# ConvertionBoard.net
KiCad netlist of a schematic drawn in Altium Designer
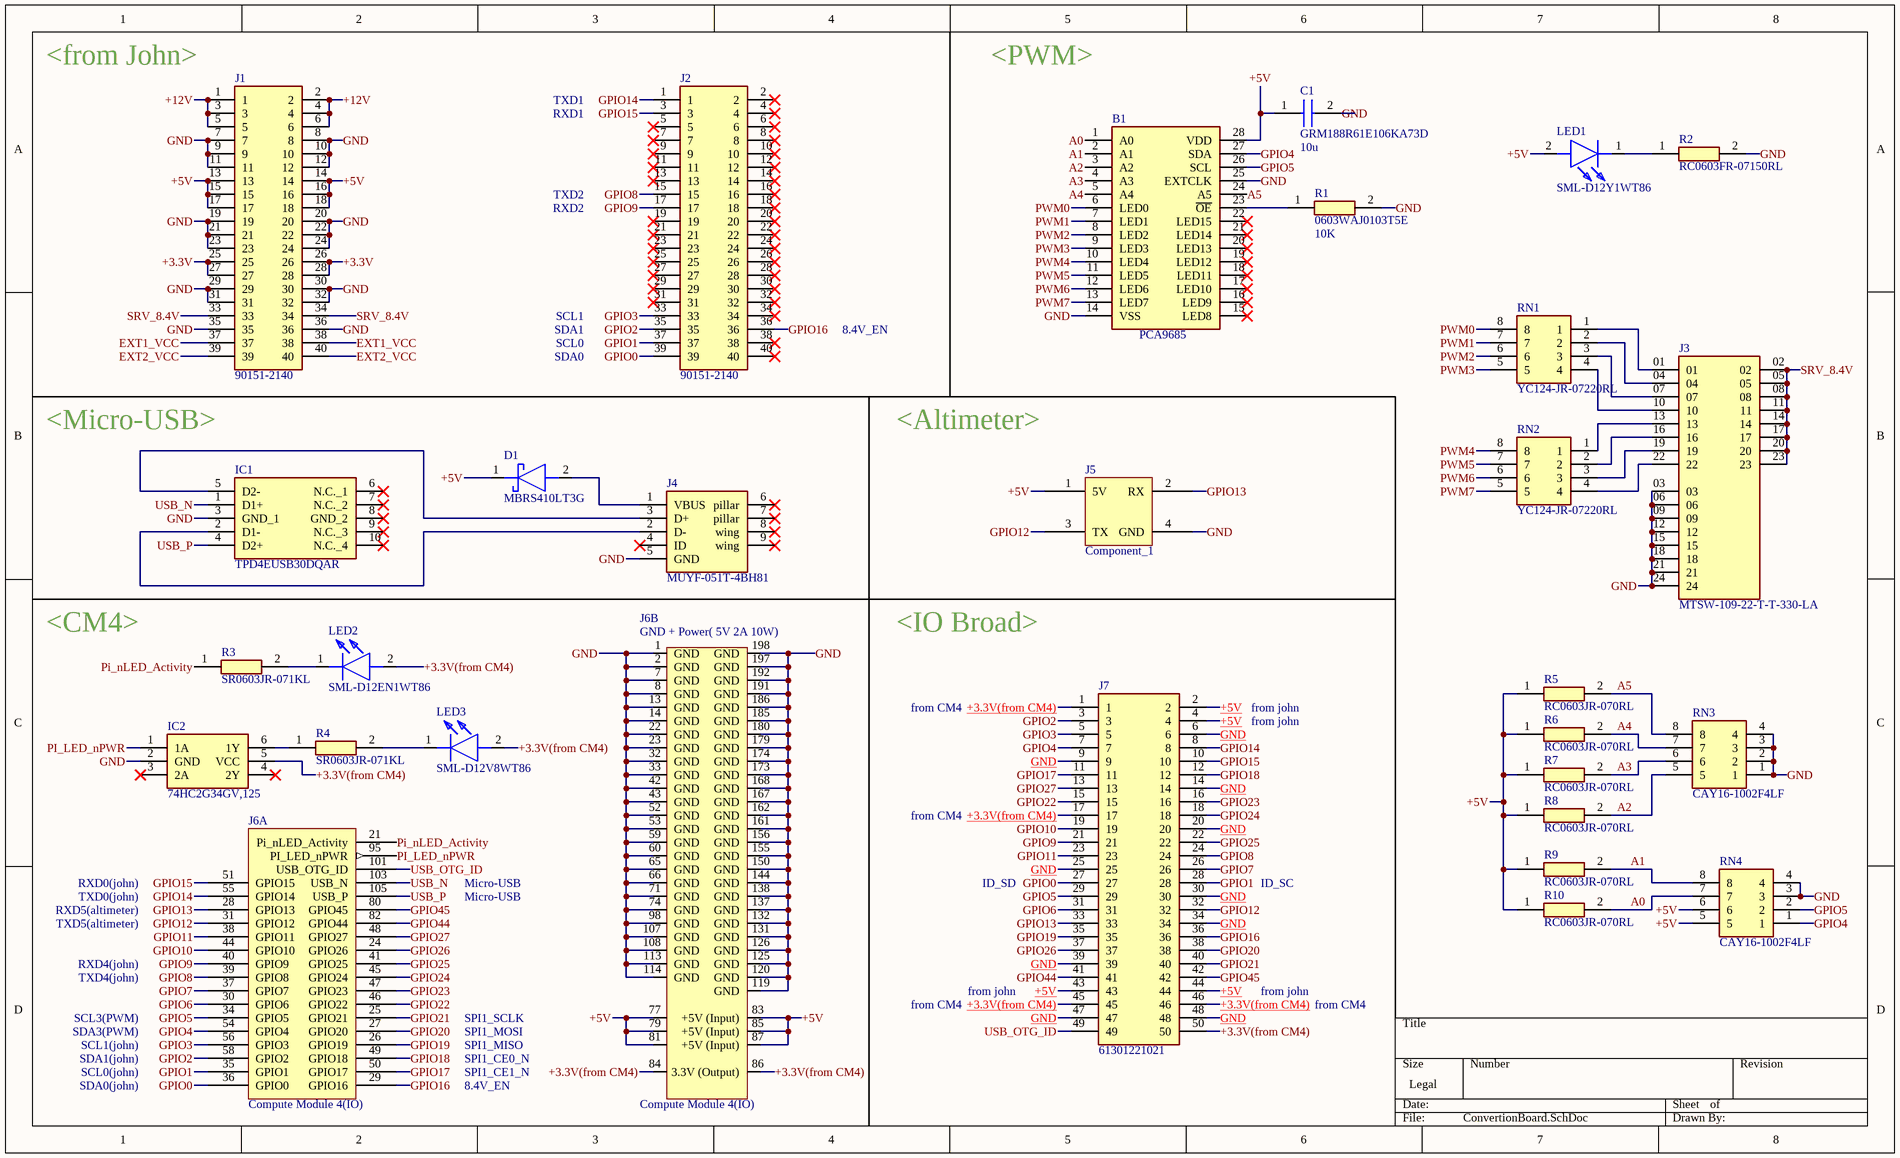
[diagram p0: ConvertionBoard.SchDoc]

(export (version "E")
  (design (tool "Eeschema 10.0.6"))
  (components
    (comp (ref "B1")
      (value "PCA9685")
      (footprint "PCA9685")
      (description "PCA9685PW/Q900,118")
      (fields (field (name "MOUSER PART NUMBER") "771-PCA9685PWQ900118"))
      (libsource (lib "ConvertionBoard") (part "PCA9685"))
    )
    (comp (ref "C1")
      (value "GRM188R61E106KA73D")
      (footprint "ConvertionBoard:GRM18x")
      (description "10% 10uF Capacitor")
      (fields (field (name "MOUSER PART NUMBER") "81-GRM188R61E106KA3D") (field (name "ALTIUM_VALUE") "10u"))
      (libsource (lib "ConvertionBoard") (part "GRM188R61E106KA73D"))
    )
    (comp (ref "D1")
      (value "MBRS410LT3G")
      (footprint "ConvertionBoard:DIOM8059X261N")
      (description "Schottky Diode")
      (fields (field (name "MOUSER PART NUMBER") "863-MBRS410LT3G"))
      (libsource (lib "ConvertionBoard") (part "MBRS410LT3G"))
    )
    (comp (ref "IC1")
      (value "TPD4EUSB30DQAR")
      (footprint "ConvertionBoard:DQA(R-PUSON-N10)")
      (description "Integrated Circuit")
      (fields (field (name "MOUSER PART NUMBER") "595-TPD4EUSB30DQAR"))
      (libsource (lib "ConvertionBoard") (part "TPD4EUSB30DQAR"))
    )
    (comp (ref "IC2")
      (value "74HC2G34GV,125")
      (footprint "ConvertionBoard:SOT95P275X110-6N")
      (description "Integrated Circuit")
      (fields (field (name "MOUSER PART NUMBER") "771-HC2G34GV125"))
      (libsource (lib "ConvertionBoard") (part "74HC2G34GV,125"))
    )
    (comp (ref "J1")
      (value "90151-2140")
      (footprint "RHDR40W70P254_2X20_5065X498X870P")
      (description "Headers")
      (fields (field (name "MOUSER PART NUMBER") "538-90151-2140"))
      (libsource (lib "ConvertionBoard") (part "90151-2140"))
    )
    (comp (ref "J2")
      (value "90151-2140")
      (footprint "RHDR40W70P254_2X20_5065X498X870P")
      (description "Headers")
      (fields (field (name "MOUSER PART NUMBER") "538-90151-2140"))
      (libsource (lib "ConvertionBoard") (part "90151-2140"))
    )
    (comp (ref "J3")
      (value "MTSW-109-22-T-T-330-LA")
      (footprint "SAMTEC_MTSW-109-22-T-T-330-LA")
      (description "PWM model pin")
      (fields (field (name "MF") "Samtec"))
      (libsource (lib "ConvertionBoard") (part "MTSW-109-22-T-T-330-LA"))
    )
    (comp (ref "J4")
      (value "MUYF-051T-4BH81")
      (footprint "ConvertionBoard:473460001")
      (description "Micro USB")
      (fields
        (field (name "MANUFACTURER_PART_NUMBER") "47346-0001")
        (field (name "MOUSER PART NUMBER") "538-47346-0001")
      )
      (libsource (lib "ConvertionBoard") (part "MUYF-051T-4BH81"))
    )
    (comp (ref "J5")
      (value "Component_1")
      (footprint "Component_1")
      (description "Altimeter pin")
      (libsource (lib "ConvertionBoard") (part "Component_1"))
    )
    (comp (ref "J6")
      (value "Compute Module 4(IO)")
      (footprint "CM4-F40C-100DS-0.4v_1.5mm_0mm")
      (libsource (lib "ConvertionBoard") (part "CM4_ALL"))
    )
    (comp (ref "J7")
      (value "61301221021")
      (footprint "ConvertionBoard:61301221021 - output")
      (description "IO broad pin")
      (fields (field (name "MOUSER PART NUMBER") "710-61301221021"))
      (libsource (lib "ConvertionBoard") (part "61301221021"))
    )
    (comp (ref "LED1")
      (value "SML-D12Y1WT86")
      (footprint "ConvertionBoard:LEDC1608X55N")
      (description "Yellow LED (connect with 150ohm)")
      (fields (field (name "MOUSER PART NUMBER") "755-SML-D12Y1WT86"))
      (libsource (lib "ConvertionBoard") (part "SML-D12Y1WT86"))
    )
    (comp (ref "LED2")
      (value "SML-D12EN1WT86")
      (footprint "ConvertionBoard:LEDC1608X55N")
      (description "Green LED (connect with 1Kohm)")
      (fields
        (field (name "MANUFACTURER_PART_NUMBER") "SMLD12EN1WT86")
        (field (name "MOUSER PART NUMBER") "755-SMLD12EN1WT86")
      )
      (libsource (lib "ConvertionBoard") (part "SML-D12EN1WT86"))
    )
    (comp (ref "LED3")
      (value "SML-D12V8WT86")
      (footprint "ConvertionBoard:LEDC1608X55N")
      (description "Red LED (connect with 1Kohm)")
      (fields (field (name "MOUSER PART NUMBER") "755-SML-D12V8WT86"))
      (libsource (lib "ConvertionBoard") (part "SML-D12V8WT86"))
    )
    (comp (ref "R1")
      (value "0603WAJ0103T5E")
      (footprint "RESC1608X55N_10K")
      (description "5% 10K Resistor")
      (fields (field (name "MOUSER PART NUMBER") "303-0603WAJ0103T5E") (field (name "ALTIUM_VALUE") "10K"))
      (libsource (lib "ConvertionBoard") (part "0603WAJ0103T5E"))
    )
    (comp (ref "R2")
      (value "RC0603FR-07150RL")
      (footprint "ConvertionBoard:RESC1608X55N_150")
      (description "1% 150 Resistor")
      (fields (field (name "MOUSER PART NUMBER") "603-RC0603FR-07150RL"))
      (libsource (lib "ConvertionBoard") (part "RC0603FR-07150RL"))
    )
    (comp (ref "R3")
      (value "SR0603JR-071KL")
      (footprint "ConvertionBoard:RESC1608X55N_0")
      (description "5% 1K Resistor")
      (fields
        (field (name "MANUFACTURER_PART_NUMBER") "RC0603JR-070RL")
        (field (name "MOUSER PART NUMBER") "603-RC0603JR-070RL")
      )
      (libsource (lib "ConvertionBoard") (part "SR0603JR-071KL"))
    )
    (comp (ref "R4")
      (value "SR0603JR-071KL")
      (footprint "ConvertionBoard:RESC1608X55N_0")
      (description "5% 1K Resistor")
      (fields
        (field (name "MANUFACTURER_PART_NUMBER") "RC0603JR-070RL")
        (field (name "MOUSER PART NUMBER") "603-RC0603JR-070RL")
      )
      (libsource (lib "ConvertionBoard") (part "SR0603JR-071KL"))
    )
    (comp (ref "R5")
      (value "RC0603JR-070RL")
      (footprint "ConvertionBoard:RESC1608X55N_0")
      (description "5% 0 Resistor")
      (fields (field (name "MOUSER PART NUMBER") "603-RC0603JR-070RL"))
      (libsource (lib "ConvertionBoard") (part "RC0603JR-070RL"))
    )
    (comp (ref "R6")
      (value "RC0603JR-070RL")
      (footprint "ConvertionBoard:RESC1608X55N_0")
      (description "5% 0 Resistor")
      (fields (field (name "MOUSER PART NUMBER") "603-RC0603JR-070RL"))
      (libsource (lib "ConvertionBoard") (part "RC0603JR-070RL"))
    )
    (comp (ref "R7")
      (value "RC0603JR-070RL")
      (footprint "ConvertionBoard:RESC1608X55N_0")
      (description "5% 0 Resistor")
      (fields (field (name "MOUSER PART NUMBER") "603-RC0603JR-070RL"))
      (libsource (lib "ConvertionBoard") (part "RC0603JR-070RL"))
    )
    (comp (ref "R8")
      (value "RC0603JR-070RL")
      (footprint "ConvertionBoard:RESC1608X55N_0")
      (description "5% 0 Resistor")
      (fields (field (name "MOUSER PART NUMBER") "603-RC0603JR-070RL"))
      (libsource (lib "ConvertionBoard") (part "RC0603JR-070RL"))
    )
    (comp (ref "R9")
      (value "RC0603JR-070RL")
      (footprint "ConvertionBoard:RESC1608X55N_0")
      (description "5% 0 Resistor")
      (fields (field (name "MOUSER PART NUMBER") "603-RC0603JR-070RL"))
      (libsource (lib "ConvertionBoard") (part "RC0603JR-070RL"))
    )
    (comp (ref "R10")
      (value "RC0603JR-070RL")
      (footprint "ConvertionBoard:RESC1608X55N_0")
      (description "5% 0 Resistor")
      (fields (field (name "MOUSER PART NUMBER") "603-RC0603JR-070RL"))
      (libsource (lib "ConvertionBoard") (part "RC0603JR-070RL"))
    )
    (comp (ref "RN1")
      (value "YC124-JR-07220RL")
      (footprint "ConvertionBoard:YC124JR07220RL")
      (description "5％ 220 Resistor Network")
      (libsource (lib "") (part "YC124-JR-07220RL_1"))
    )
    (comp (ref "RN2")
      (value "YC124-JR-07220RL")
      (footprint "ConvertionBoard:YC124JR07220RL")
      (description "5％ 220 Resistor Network")
      (libsource (lib "ConvertionBoard") (part "YC124-JR-07220RL"))
    )
    (comp (ref "RN3")
      (value "CAY16-1002F4LF")
      (footprint "ConvertionBoard:CAY-16-F4")
      (description "1% 10K Resistor Network(lab have)")
      (fields (field (name "MOUSER PART NUMBER") "652-CAY16-1002F4LF"))
      (libsource (lib "ConvertionBoard") (part "CAY16-1002F4LF"))
    )
    (comp (ref "RN4")
      (value "CAY16-1002F4LF")
      (footprint "ConvertionBoard:CAY-16-F4")
      (description "1% 10K Resistor Network(lab have)")
      (fields (field (name "MOUSER PART NUMBER") "652-CAY16-1002F4LF"))
      (libsource (lib "ConvertionBoard") (part "CAY16-1002F4LF"))
    )
  )
  (nets
    (net (code "1") (name "/+3.3V") (class "Default")
      (node (ref "J1") (pin "25") (pinfunction "25_25") (pintype "passive"))
      (node (ref "J1") (pin "26") (pinfunction "26_26") (pintype "passive"))
      (node (ref "J1") (pin "27") (pinfunction "27_27") (pintype "passive"))
      (node (ref "J1") (pin "28") (pinfunction "28_28") (pintype "passive"))
    )
    (net (code "2") (name "/+3.3V(from CM4)") (class "Default")
      (node (ref "IC2") (pin "5") (pinfunction "VCC_5") (pintype "passive"))
      (node (ref "J6") (pin "84") (pinfunction "3.3V_(Output)_84") (pintype "power_in"))
      (node (ref "J6") (pin "86") (pinfunction "3.3V_(Output)_86") (pintype "power_in"))
      (node (ref "J7") (pin "1") (pinfunction "1_1") (pintype "passive"))
      (node (ref "J7") (pin "17") (pinfunction "17_17") (pintype "passive"))
      (node (ref "J7") (pin "45") (pinfunction "45_45") (pintype "passive"))
      (node (ref "J7") (pin "46") (pinfunction "46_46") (pintype "passive"))
      (node (ref "J7") (pin "50") (pinfunction "50_50") (pintype "passive"))
      (node (ref "LED2") (pin "2") (pinfunction "A_2") (pintype "passive"))
      (node (ref "LED3") (pin "2") (pinfunction "A_2") (pintype "passive"))
    )
    (net (code "3") (name "/+5V") (class "Default")
      (node (ref "B1") (pin "28") (pinfunction "VDD_28") (pintype "passive"))
      (node (ref "C1") (pin "1") (pinfunction "1_1") (pintype "passive"))
      (node (ref "D1") (pin "1") (pinfunction "K_1") (pintype "passive"))
      (node (ref "J1") (pin "13") (pinfunction "13_13") (pintype "passive"))
      (node (ref "J1") (pin "14") (pinfunction "14_14") (pintype "passive"))
      (node (ref "J1") (pin "15") (pinfunction "15_15") (pintype "passive"))
      (node (ref "J1") (pin "16") (pinfunction "16_16") (pintype "passive"))
      (node (ref "J1") (pin "17") (pinfunction "17_17") (pintype "passive"))
      (node (ref "J1") (pin "18") (pinfunction "18_18") (pintype "passive"))
      (node (ref "J5") (pin "1") (pinfunction "5V_1") (pintype "passive"))
      (node (ref "J6") (pin "77") (pinfunction "+5V_(Input)_77") (pintype "power_in"))
      (node (ref "J6") (pin "79") (pinfunction "+5V_(Input)_79") (pintype "power_in"))
      (node (ref "J6") (pin "81") (pinfunction "+5V_(Input)_81") (pintype "power_in"))
      (node (ref "J6") (pin "83") (pinfunction "+5V_(Input)_83") (pintype "power_in"))
      (node (ref "J6") (pin "85") (pinfunction "+5V_(Input)_85") (pintype "power_in"))
      (node (ref "J6") (pin "87") (pinfunction "+5V_(Input)_87") (pintype "power_in"))
      (node (ref "J7") (pin "2") (pinfunction "2_2") (pintype "passive"))
      (node (ref "J7") (pin "4") (pinfunction "4_4") (pintype "passive"))
      (node (ref "J7") (pin "43") (pinfunction "43_43") (pintype "passive"))
      (node (ref "J7") (pin "44") (pinfunction "44_44") (pintype "passive"))
      (node (ref "LED1") (pin "2") (pinfunction "A_2") (pintype "passive"))
      (node (ref "R10") (pin "1") (pinfunction "1_1") (pintype "passive"))
      (node (ref "R5") (pin "1") (pinfunction "1_1") (pintype "passive"))
      (node (ref "R6") (pin "1") (pinfunction "1_1") (pintype "passive"))
      (node (ref "R7") (pin "1") (pinfunction "1_1") (pintype "passive"))
      (node (ref "R8") (pin "1") (pinfunction "1_1") (pintype "passive"))
      (node (ref "R9") (pin "1") (pinfunction "1_1") (pintype "passive"))
      (node (ref "RN4") (pin "5") (pinfunction "5_5") (pintype "passive"))
      (node (ref "RN4") (pin "6") (pinfunction "6_6") (pintype "passive"))
    )
    (net (code "4") (name "/+12V") (class "Default")
      (node (ref "J1") (pin "1") (pinfunction "1_1") (pintype "passive"))
      (node (ref "J1") (pin "2") (pinfunction "2_2") (pintype "passive"))
      (node (ref "J1") (pin "3") (pinfunction "3_3") (pintype "passive"))
      (node (ref "J1") (pin "4") (pinfunction "4_4") (pintype "passive"))
      (node (ref "J1") (pin "5") (pinfunction "5_5") (pintype "passive"))
      (node (ref "J1") (pin "6") (pinfunction "6_6") (pintype "passive"))
    )
    (net (code "5") (name "/A0") (class "Default")
      (node (ref "B1") (pin "1") (pinfunction "A0_1") (pintype "passive"))
      (node (ref "R10") (pin "2") (pinfunction "2_2") (pintype "passive"))
      (node (ref "RN4") (pin "7") (pinfunction "7_7") (pintype "passive"))
    )
    (net (code "6") (name "/A1") (class "Default")
      (node (ref "B1") (pin "2") (pinfunction "A1_2") (pintype "passive"))
      (node (ref "R9") (pin "2") (pinfunction "2_2") (pintype "passive"))
      (node (ref "RN4") (pin "8") (pinfunction "8_8") (pintype "passive"))
    )
    (net (code "7") (name "/A2") (class "Default")
      (node (ref "B1") (pin "3") (pinfunction "A2_3") (pintype "passive"))
      (node (ref "R8") (pin "2") (pinfunction "2_2") (pintype "passive"))
      (node (ref "RN3") (pin "5") (pinfunction "5_5") (pintype "passive"))
    )
    (net (code "8") (name "/A3") (class "Default")
      (node (ref "B1") (pin "4") (pinfunction "A3_4") (pintype "passive"))
      (node (ref "R7") (pin "2") (pinfunction "2_2") (pintype "passive"))
      (node (ref "RN3") (pin "6") (pinfunction "6_6") (pintype "passive"))
    )
    (net (code "9") (name "/A4") (class "Default")
      (node (ref "B1") (pin "5") (pinfunction "A4_5") (pintype "passive"))
      (node (ref "R6") (pin "2") (pinfunction "2_2") (pintype "passive"))
      (node (ref "RN3") (pin "7") (pinfunction "7_7") (pintype "passive"))
    )
    (net (code "10") (name "/A5") (class "Default")
      (node (ref "B1") (pin "24") (pinfunction "A5_24") (pintype "passive"))
      (node (ref "R5") (pin "2") (pinfunction "2_2") (pintype "passive"))
      (node (ref "RN3") (pin "8") (pinfunction "8_8") (pintype "passive"))
    )
    (net (code "11") (name "/EXT1_VCC") (class "Default")
      (node (ref "J1") (pin "37") (pinfunction "37_37") (pintype "passive"))
      (node (ref "J1") (pin "38") (pinfunction "38_38") (pintype "passive"))
    )
    (net (code "12") (name "/EXT2_VCC") (class "Default")
      (node (ref "J1") (pin "39") (pinfunction "39_39") (pintype "passive"))
      (node (ref "J1") (pin "40") (pinfunction "40_40") (pintype "passive"))
    )
    (net (code "13") (name "/GND") (class "Default")
      (node (ref "B1") (pin "14") (pinfunction "VSS_14") (pintype "passive"))
      (node (ref "B1") (pin "25") (pinfunction "EXTCLK_25") (pintype "passive"))
      (node (ref "C1") (pin "2") (pinfunction "2_2") (pintype "passive"))
      (node (ref "IC1") (pin "3") (pinfunction "GND_1_3") (pintype "passive"))
      (node (ref "IC2") (pin "2") (pinfunction "GND_2") (pintype "passive"))
      (node (ref "J1") (pin "10") (pinfunction "10_10") (pintype "passive"))
      (node (ref "J1") (pin "11") (pinfunction "11_11") (pintype "passive"))
      (node (ref "J1") (pin "12") (pinfunction "12_12") (pintype "passive"))
      (node (ref "J1") (pin "19") (pinfunction "19_19") (pintype "passive"))
      (node (ref "J1") (pin "20") (pinfunction "20_20") (pintype "passive"))
      (node (ref "J1") (pin "21") (pinfunction "21_21") (pintype "passive"))
      (node (ref "J1") (pin "22") (pinfunction "22_22") (pintype "passive"))
      (node (ref "J1") (pin "23") (pinfunction "23_23") (pintype "passive"))
      (node (ref "J1") (pin "24") (pinfunction "24_24") (pintype "passive"))
      (node (ref "J1") (pin "29") (pinfunction "29_29") (pintype "passive"))
      (node (ref "J1") (pin "30") (pinfunction "30_30") (pintype "passive"))
      (node (ref "J1") (pin "31") (pinfunction "31_31") (pintype "passive"))
      (node (ref "J1") (pin "32") (pinfunction "32_32") (pintype "passive"))
      (node (ref "J1") (pin "35") (pinfunction "35_35") (pintype "passive"))
      (node (ref "J1") (pin "36") (pinfunction "36_36") (pintype "passive"))
      (node (ref "J1") (pin "7") (pinfunction "7_7") (pintype "passive"))
      (node (ref "J1") (pin "8") (pinfunction "8_8") (pintype "passive"))
      (node (ref "J1") (pin "9") (pinfunction "9_9") (pintype "passive"))
      (node (ref "J3") (pin "03") (pinfunction "03_03") (pintype "passive"))
      (node (ref "J3") (pin "06") (pinfunction "06_06") (pintype "passive"))
      (node (ref "J3") (pin "09") (pinfunction "09_09") (pintype "passive"))
      (node (ref "J3") (pin "12") (pinfunction "12_12") (pintype "passive"))
      (node (ref "J3") (pin "15") (pinfunction "15_15") (pintype "passive"))
      (node (ref "J3") (pin "18") (pinfunction "18_18") (pintype "passive"))
      (node (ref "J3") (pin "21") (pinfunction "21_21") (pintype "passive"))
      (node (ref "J3") (pin "24") (pinfunction "24_24") (pintype "passive"))
      (node (ref "J4") (pin "5") (pinfunction "GND_5") (pintype "passive"))
      (node (ref "J5") (pin "4") (pinfunction "GND_4") (pintype "passive"))
      (node (ref "J6") (pin "1") (pinfunction "GND_1") (pintype "power_in"))
      (node (ref "J6") (pin "107") (pinfunction "GND_107") (pintype "power_in"))
      (node (ref "J6") (pin "108") (pinfunction "GND_108") (pintype "power_in"))
      (node (ref "J6") (pin "113") (pinfunction "GND_113") (pintype "power_in"))
      (node (ref "J6") (pin "114") (pinfunction "GND_114") (pintype "power_in"))
      (node (ref "J6") (pin "119") (pinfunction "GND_119") (pintype "power_in"))
      (node (ref "J6") (pin "120") (pinfunction "GND_120") (pintype "power_in"))
      (node (ref "J6") (pin "125") (pinfunction "GND_125") (pintype "power_in"))
      (node (ref "J6") (pin "126") (pinfunction "GND_126") (pintype "power_in"))
      (node (ref "J6") (pin "13") (pinfunction "GND_13") (pintype "power_in"))
      (node (ref "J6") (pin "131") (pinfunction "GND_131") (pintype "power_in"))
      (node (ref "J6") (pin "132") (pinfunction "GND_132") (pintype "power_in"))
      (node (ref "J6") (pin "137") (pinfunction "GND_137") (pintype "power_in"))
      (node (ref "J6") (pin "138") (pinfunction "GND_138") (pintype "power_in"))
      (node (ref "J6") (pin "14") (pinfunction "GND_14") (pintype "power_in"))
      (node (ref "J6") (pin "144") (pinfunction "GND_144") (pintype "power_in"))
      (node (ref "J6") (pin "150") (pinfunction "GND_150") (pintype "power_in"))
      (node (ref "J6") (pin "155") (pinfunction "GND_155") (pintype "power_in"))
      (node (ref "J6") (pin "156") (pinfunction "GND_156") (pintype "power_in"))
      (node (ref "J6") (pin "161") (pinfunction "GND_161") (pintype "power_in"))
      (node (ref "J6") (pin "162") (pinfunction "GND_162") (pintype "power_in"))
      (node (ref "J6") (pin "167") (pinfunction "GND_167") (pintype "power_in"))
      (node (ref "J6") (pin "168") (pinfunction "GND_168") (pintype "power_in"))
      (node (ref "J6") (pin "173") (pinfunction "GND_173") (pintype "power_in"))
      (node (ref "J6") (pin "174") (pinfunction "GND_174") (pintype "power_in"))
      (node (ref "J6") (pin "179") (pinfunction "GND_179") (pintype "power_in"))
      (node (ref "J6") (pin "180") (pinfunction "GND_180") (pintype "power_in"))
      (node (ref "J6") (pin "185") (pinfunction "GND_185") (pintype "power_in"))
      (node (ref "J6") (pin "186") (pinfunction "GND_186") (pintype "power_in"))
      (node (ref "J6") (pin "191") (pinfunction "GND_191") (pintype "power_in"))
      (node (ref "J6") (pin "192") (pinfunction "GND_192") (pintype "power_in"))
      (node (ref "J6") (pin "197") (pinfunction "GND_197") (pintype "power_in"))
      (node (ref "J6") (pin "198") (pinfunction "GND_198") (pintype "power_in"))
      (node (ref "J6") (pin "2") (pinfunction "GND_2") (pintype "power_in"))
      (node (ref "J6") (pin "22") (pinfunction "GND_22") (pintype "power_in"))
      (node (ref "J6") (pin "23") (pinfunction "GND_23") (pintype "power_in"))
      (node (ref "J6") (pin "32") (pinfunction "GND_32") (pintype "power_in"))
      (node (ref "J6") (pin "33") (pinfunction "GND_33") (pintype "power_in"))
      (node (ref "J6") (pin "42") (pinfunction "GND_42") (pintype "power_in"))
      (node (ref "J6") (pin "43") (pinfunction "GND_43") (pintype "power_in"))
      (node (ref "J6") (pin "52") (pinfunction "GND_52") (pintype "power_in"))
      (node (ref "J6") (pin "53") (pinfunction "GND_53") (pintype "power_in"))
      (node (ref "J6") (pin "59") (pinfunction "GND_59") (pintype "power_in"))
      (node (ref "J6") (pin "60") (pinfunction "GND_60") (pintype "power_in"))
      (node (ref "J6") (pin "65") (pinfunction "GND_65") (pintype "power_in"))
      (node (ref "J6") (pin "66") (pinfunction "GND_66") (pintype "power_in"))
      (node (ref "J6") (pin "7") (pinfunction "GND_7") (pintype "power_in"))
      (node (ref "J6") (pin "71") (pinfunction "GND_71") (pintype "power_in"))
      (node (ref "J6") (pin "74") (pinfunction "GND_74") (pintype "power_in"))
      (node (ref "J6") (pin "8") (pinfunction "GND_8") (pintype "power_in"))
      (node (ref "J6") (pin "98") (pinfunction "GND_98") (pintype "power_in"))
      (node (ref "J7") (pin "14") (pinfunction "14_14") (pintype "passive"))
      (node (ref "J7") (pin "20") (pinfunction "20_20") (pintype "passive"))
      (node (ref "J7") (pin "25") (pinfunction "25_25") (pintype "passive"))
      (node (ref "J7") (pin "30") (pinfunction "30_30") (pintype "passive"))
      (node (ref "J7") (pin "34") (pinfunction "34_34") (pintype "passive"))
      (node (ref "J7") (pin "39") (pinfunction "39_39") (pintype "passive"))
      (node (ref "J7") (pin "47") (pinfunction "47_47") (pintype "passive"))
      (node (ref "J7") (pin "48") (pinfunction "48_48") (pintype "passive"))
      (node (ref "J7") (pin "6") (pinfunction "6_6") (pintype "passive"))
      (node (ref "J7") (pin "9") (pinfunction "9_9") (pintype "passive"))
      (node (ref "R1") (pin "2") (pinfunction "2_2") (pintype "passive"))
      (node (ref "R2") (pin "2") (pinfunction "2_2") (pintype "passive"))
      (node (ref "RN3") (pin "1") (pinfunction "1_1") (pintype "passive"))
      (node (ref "RN3") (pin "2") (pinfunction "2_2") (pintype "passive"))
      (node (ref "RN3") (pin "3") (pinfunction "3_3") (pintype "passive"))
      (node (ref "RN3") (pin "4") (pinfunction "4_4") (pintype "passive"))
      (node (ref "RN4") (pin "3") (pinfunction "3_3") (pintype "passive"))
      (node (ref "RN4") (pin "4") (pinfunction "4_4") (pintype "passive"))
    )
    (net (code "14") (name "/GPIO0") (class "Default")
      (node (ref "J2") (pin "39") (pinfunction "39_39") (pintype "passive"))
      (node (ref "J6") (pin "36") (pinfunction "GPIO0_36") (pintype "passive"))
      (node (ref "J7") (pin "27") (pinfunction "27_27") (pintype "passive"))
    )
    (net (code "15") (name "/GPIO1") (class "Default")
      (node (ref "J2") (pin "37") (pinfunction "37_37") (pintype "passive"))
      (node (ref "J6") (pin "35") (pinfunction "GPIO1_35") (pintype "passive"))
      (node (ref "J7") (pin "28") (pinfunction "28_28") (pintype "passive"))
    )
    (net (code "16") (name "/GPIO2") (class "Default")
      (node (ref "J2") (pin "35") (pinfunction "35_35") (pintype "passive"))
      (node (ref "J6") (pin "58") (pinfunction "GPIO2_58") (pintype "passive"))
      (node (ref "J7") (pin "3") (pinfunction "3_3") (pintype "passive"))
    )
    (net (code "17") (name "/GPIO3") (class "Default")
      (node (ref "J2") (pin "33") (pinfunction "33_33") (pintype "passive"))
      (node (ref "J6") (pin "56") (pinfunction "GPIO3_56") (pintype "passive"))
      (node (ref "J7") (pin "5") (pinfunction "5_5") (pintype "passive"))
    )
    (net (code "18") (name "/GPIO4") (class "Default")
      (node (ref "B1") (pin "27") (pinfunction "SDA_27") (pintype "passive"))
      (node (ref "J6") (pin "54") (pinfunction "GPIO4_54") (pintype "passive"))
      (node (ref "J7") (pin "7") (pinfunction "7_7") (pintype "passive"))
      (node (ref "RN4") (pin "1") (pinfunction "1_1") (pintype "passive"))
    )
    (net (code "19") (name "/GPIO5") (class "Default")
      (node (ref "B1") (pin "26") (pinfunction "SCL_26") (pintype "passive"))
      (node (ref "J6") (pin "34") (pinfunction "GPIO5_34") (pintype "passive"))
      (node (ref "J7") (pin "29") (pinfunction "29_29") (pintype "passive"))
      (node (ref "RN4") (pin "2") (pinfunction "2_2") (pintype "passive"))
    )
    (net (code "20") (name "/GPIO6") (class "Default")
      (node (ref "J6") (pin "30") (pinfunction "GPIO6_30") (pintype "passive"))
      (node (ref "J7") (pin "31") (pinfunction "31_31") (pintype "passive"))
    )
    (net (code "21") (name "/GPIO7") (class "Default")
      (node (ref "J6") (pin "37") (pinfunction "GPIO7_37") (pintype "passive"))
      (node (ref "J7") (pin "26") (pinfunction "26_26") (pintype "passive"))
    )
    (net (code "22") (name "/GPIO8") (class "Default")
      (node (ref "J2") (pin "15") (pinfunction "15_15") (pintype "passive"))
      (node (ref "J6") (pin "39") (pinfunction "GPIO8_39") (pintype "passive"))
      (node (ref "J7") (pin "24") (pinfunction "24_24") (pintype "passive"))
    )
    (net (code "23") (name "/GPIO9") (class "Default")
      (node (ref "J2") (pin "17") (pinfunction "17_17") (pintype "passive"))
      (node (ref "J6") (pin "40") (pinfunction "GPIO9_40") (pintype "passive"))
      (node (ref "J7") (pin "21") (pinfunction "21_21") (pintype "passive"))
    )
    (net (code "24") (name "/GPIO10") (class "Default")
      (node (ref "J6") (pin "44") (pinfunction "GPIO10_44") (pintype "passive"))
      (node (ref "J7") (pin "19") (pinfunction "19_19") (pintype "passive"))
    )
    (net (code "25") (name "/GPIO11") (class "Default")
      (node (ref "J6") (pin "38") (pinfunction "GPIO11_38") (pintype "passive"))
      (node (ref "J7") (pin "23") (pinfunction "23_23") (pintype "passive"))
    )
    (net (code "26") (name "/GPIO12") (class "Default")
      (node (ref "J5") (pin "3") (pinfunction "TX_3") (pintype "passive"))
      (node (ref "J6") (pin "31") (pinfunction "GPIO12_31") (pintype "passive"))
      (node (ref "J7") (pin "32") (pinfunction "32_32") (pintype "passive"))
    )
    (net (code "27") (name "/GPIO13") (class "Default")
      (node (ref "J5") (pin "2") (pinfunction "RX_2") (pintype "passive"))
      (node (ref "J6") (pin "28") (pinfunction "GPIO13_28") (pintype "passive"))
      (node (ref "J7") (pin "33") (pinfunction "33_33") (pintype "passive"))
    )
    (net (code "28") (name "/GPIO14") (class "Default")
      (node (ref "J2") (pin "1") (pinfunction "1_1") (pintype "passive"))
      (node (ref "J6") (pin "55") (pinfunction "GPIO14_55") (pintype "passive"))
      (node (ref "J7") (pin "8") (pinfunction "8_8") (pintype "passive"))
    )
    (net (code "29") (name "/GPIO15") (class "Default")
      (node (ref "J2") (pin "3") (pinfunction "3_3") (pintype "passive"))
      (node (ref "J6") (pin "51") (pinfunction "GPIO15_51") (pintype "passive"))
      (node (ref "J7") (pin "10") (pinfunction "10_10") (pintype "passive"))
    )
    (net (code "30") (name "/GPIO16") (class "Default")
      (node (ref "J2") (pin "36") (pinfunction "36_36") (pintype "passive"))
      (node (ref "J6") (pin "29") (pinfunction "GPIO16_29") (pintype "passive"))
      (node (ref "J7") (pin "36") (pinfunction "36_36") (pintype "passive"))
    )
    (net (code "31") (name "/GPIO17") (class "Default")
      (node (ref "J6") (pin "50") (pinfunction "GPIO17_50") (pintype "passive"))
      (node (ref "J7") (pin "11") (pinfunction "11_11") (pintype "passive"))
    )
    (net (code "32") (name "/GPIO18") (class "Default")
      (node (ref "J6") (pin "49") (pinfunction "GPIO18_49") (pintype "passive"))
      (node (ref "J7") (pin "12") (pinfunction "12_12") (pintype "passive"))
    )
    (net (code "33") (name "/GPIO19") (class "Default")
      (node (ref "J6") (pin "26") (pinfunction "GPIO19_26") (pintype "passive"))
      (node (ref "J7") (pin "35") (pinfunction "35_35") (pintype "passive"))
    )
    (net (code "34") (name "/GPIO20") (class "Default")
      (node (ref "J6") (pin "27") (pinfunction "GPIO20_27") (pintype "passive"))
      (node (ref "J7") (pin "38") (pinfunction "38_38") (pintype "passive"))
    )
    (net (code "35") (name "/GPIO21") (class "Default")
      (node (ref "J6") (pin "25") (pinfunction "GPIO21_25") (pintype "passive"))
      (node (ref "J7") (pin "40") (pinfunction "40_40") (pintype "passive"))
    )
    (net (code "36") (name "/GPIO22") (class "Default")
      (node (ref "J6") (pin "46") (pinfunction "GPIO22_46") (pintype "passive"))
      (node (ref "J7") (pin "15") (pinfunction "15_15") (pintype "passive"))
    )
    (net (code "37") (name "/GPIO23") (class "Default")
      (node (ref "J6") (pin "47") (pinfunction "GPIO23_47") (pintype "passive"))
      (node (ref "J7") (pin "16") (pinfunction "16_16") (pintype "passive"))
    )
    (net (code "38") (name "/GPIO24") (class "Default")
      (node (ref "J6") (pin "45") (pinfunction "GPIO24_45") (pintype "passive"))
      (node (ref "J7") (pin "18") (pinfunction "18_18") (pintype "passive"))
    )
    (net (code "39") (name "/GPIO25") (class "Default")
      (node (ref "J6") (pin "41") (pinfunction "GPIO25_41") (pintype "passive"))
      (node (ref "J7") (pin "22") (pinfunction "22_22") (pintype "passive"))
    )
    (net (code "40") (name "/GPIO26") (class "Default")
      (node (ref "J6") (pin "24") (pinfunction "GPIO26_24") (pintype "passive"))
      (node (ref "J7") (pin "37") (pinfunction "37_37") (pintype "passive"))
    )
    (net (code "41") (name "/GPIO27") (class "Default")
      (node (ref "J6") (pin "48") (pinfunction "GPIO27_48") (pintype "passive"))
      (node (ref "J7") (pin "13") (pinfunction "13_13") (pintype "passive"))
    )
    (net (code "42") (name "/GPIO44") (class "Default")
      (node (ref "J6") (pin "82") (pinfunction "GPIO44_82") (pintype "passive"))
      (node (ref "J7") (pin "41") (pinfunction "41_41") (pintype "passive"))
    )
    (net (code "43") (name "/GPIO45") (class "Default")
      (node (ref "J6") (pin "80") (pinfunction "GPIO45_80") (pintype "passive"))
      (node (ref "J7") (pin "42") (pinfunction "42_42") (pintype "passive"))
    )
    (net (code "44") (name "/PI_LED_nPWR") (class "Default")
      (node (ref "IC2") (pin "1") (pinfunction "1A_1") (pintype "passive"))
      (node (ref "J6") (pin "95") (pinfunction "PI_LED_nPWR_95") (pintype "output"))
    )
    (net (code "45") (name "/PWM0") (class "Default")
      (node (ref "B1") (pin "6") (pinfunction "LED0_6") (pintype "passive"))
      (node (ref "RN1") (pin "8") (pinfunction "8_8") (pintype "passive"))
    )
    (net (code "46") (name "/PWM1") (class "Default")
      (node (ref "B1") (pin "7") (pinfunction "LED1_7") (pintype "passive"))
      (node (ref "RN1") (pin "7") (pinfunction "7_7") (pintype "passive"))
    )
    (net (code "47") (name "/PWM2") (class "Default")
      (node (ref "B1") (pin "8") (pinfunction "LED2_8") (pintype "passive"))
      (node (ref "RN1") (pin "6") (pinfunction "6_6") (pintype "passive"))
    )
    (net (code "48") (name "/PWM3") (class "Default")
      (node (ref "B1") (pin "9") (pinfunction "LED3_9") (pintype "passive"))
      (node (ref "RN1") (pin "5") (pinfunction "5_5") (pintype "passive"))
    )
    (net (code "49") (name "/PWM4") (class "Default")
      (node (ref "B1") (pin "10") (pinfunction "LED4_10") (pintype "passive"))
      (node (ref "RN2") (pin "8") (pinfunction "8_8") (pintype "passive"))
    )
    (net (code "50") (name "/PWM5") (class "Default")
      (node (ref "B1") (pin "11") (pinfunction "LED5_11") (pintype "passive"))
      (node (ref "RN2") (pin "7") (pinfunction "7_7") (pintype "passive"))
    )
    (net (code "51") (name "/PWM6") (class "Default")
      (node (ref "B1") (pin "12") (pinfunction "LED6_12") (pintype "passive"))
      (node (ref "RN2") (pin "6") (pinfunction "6_6") (pintype "passive"))
    )
    (net (code "52") (name "/PWM7") (class "Default")
      (node (ref "B1") (pin "13") (pinfunction "LED7_13") (pintype "passive"))
      (node (ref "RN2") (pin "5") (pinfunction "5_5") (pintype "passive"))
    )
    (net (code "53") (name "/Pi_nLED_Activity") (class "Default")
      (node (ref "J6") (pin "21") (pinfunction "Pi_nLED_Activity_21") (pintype "open_collector"))
      (node (ref "R3") (pin "1") (pinfunction "1_1") (pintype "passive"))
    )
    (net (code "54") (name "/SRV_8.4V") (class "Default")
      (node (ref "J1") (pin "33") (pinfunction "33_33") (pintype "passive"))
      (node (ref "J1") (pin "34") (pinfunction "34_34") (pintype "passive"))
      (node (ref "J3") (pin "02") (pinfunction "02_02") (pintype "passive"))
      (node (ref "J3") (pin "05") (pinfunction "05_05") (pintype "passive"))
      (node (ref "J3") (pin "08") (pinfunction "08_08") (pintype "passive"))
      (node (ref "J3") (pin "11") (pinfunction "11_11") (pintype "passive"))
      (node (ref "J3") (pin "14") (pinfunction "14_14") (pintype "passive"))
      (node (ref "J3") (pin "17") (pinfunction "17_17") (pintype "passive"))
      (node (ref "J3") (pin "20") (pinfunction "20_20") (pintype "passive"))
      (node (ref "J3") (pin "23") (pinfunction "23_23") (pintype "passive"))
    )
    (net (code "55") (name "/USB_N") (class "Default")
      (node (ref "IC1") (pin "1") (pinfunction "D1+_1") (pintype "passive"))
      (node (ref "J6") (pin "103") (pinfunction "USB_N_103") (pintype "passive"))
    )
    (net (code "56") (name "/USB_OTG_ID") (class "Default")
      (node (ref "J6") (pin "101") (pinfunction "USB_OTG_ID_101") (pintype "passive"))
      (node (ref "J7") (pin "49") (pinfunction "49_49") (pintype "passive"))
    )
    (net (code "57") (name "/USB_P") (class "Default")
      (node (ref "IC1") (pin "4") (pinfunction "D2+_4") (pintype "passive"))
      (node (ref "J6") (pin "105") (pinfunction "USB_P_105") (pintype "passive"))
    )
    (net (code "58") (name "Net-(B1-~{OE})") (class "Default")
      (node (ref "B1") (pin "23") (pinfunction "~{OE}_23") (pintype "passive"))
      (node (ref "R1") (pin "1") (pinfunction "1_1") (pintype "passive"))
    )
    (net (code "59") (name "Net-(D1-A)") (class "Default")
      (node (ref "D1") (pin "2") (pinfunction "A_2") (pintype "passive"))
      (node (ref "J4") (pin "1") (pinfunction "VBUS_1") (pintype "passive"))
    )
    (net (code "60") (name "Net-(IC1-D1-)") (class "Default")
      (node (ref "IC1") (pin "2") (pinfunction "D1-_2") (pintype "passive"))
      (node (ref "J4") (pin "2") (pinfunction "D-_2") (pintype "passive"))
    )
    (net (code "61") (name "Net-(IC1-D2-)") (class "Default")
      (node (ref "IC1") (pin "5") (pinfunction "D2-_5") (pintype "passive"))
      (node (ref "J4") (pin "3") (pinfunction "D+_3") (pintype "passive"))
    )
    (net (code "62") (name "Net-(IC2-1Y)") (class "Default")
      (node (ref "IC2") (pin "6") (pinfunction "1Y_6") (pintype "passive"))
      (node (ref "R4") (pin "1") (pinfunction "1_1") (pintype "passive"))
    )
    (net (code "63") (name "Net-(J3-Pad01)") (class "Default")
      (node (ref "J3") (pin "01") (pinfunction "01_01") (pintype "passive"))
      (node (ref "RN1") (pin "1") (pinfunction "1_1") (pintype "passive"))
    )
    (net (code "64") (name "Net-(J3-Pad04)") (class "Default")
      (node (ref "J3") (pin "04") (pinfunction "04_04") (pintype "passive"))
      (node (ref "RN1") (pin "2") (pinfunction "2_2") (pintype "passive"))
    )
    (net (code "65") (name "Net-(J3-Pad07)") (class "Default")
      (node (ref "J3") (pin "07") (pinfunction "07_07") (pintype "passive"))
      (node (ref "RN1") (pin "3") (pinfunction "3_3") (pintype "passive"))
    )
    (net (code "66") (name "Net-(J3-Pad10)") (class "Default")
      (node (ref "J3") (pin "10") (pinfunction "10_10") (pintype "passive"))
      (node (ref "RN1") (pin "4") (pinfunction "4_4") (pintype "passive"))
    )
    (net (code "67") (name "Net-(J3-Pad13)") (class "Default")
      (node (ref "J3") (pin "13") (pinfunction "13_13") (pintype "passive"))
      (node (ref "RN2") (pin "1") (pinfunction "1_1") (pintype "passive"))
    )
    (net (code "68") (name "Net-(J3-Pad16)") (class "Default")
      (node (ref "J3") (pin "16") (pinfunction "16_16") (pintype "passive"))
      (node (ref "RN2") (pin "2") (pinfunction "2_2") (pintype "passive"))
    )
    (net (code "69") (name "Net-(J3-Pad19)") (class "Default")
      (node (ref "J3") (pin "19") (pinfunction "19_19") (pintype "passive"))
      (node (ref "RN2") (pin "3") (pinfunction "3_3") (pintype "passive"))
    )
    (net (code "70") (name "Net-(J3-Pad22)") (class "Default")
      (node (ref "J3") (pin "22") (pinfunction "22_22") (pintype "passive"))
      (node (ref "RN2") (pin "4") (pinfunction "4_4") (pintype "passive"))
    )
    (net (code "71") (name "Net-(LED1-K)") (class "Default")
      (node (ref "LED1") (pin "1") (pinfunction "K_1") (pintype "passive"))
      (node (ref "R2") (pin "1") (pinfunction "1_1") (pintype "passive"))
    )
    (net (code "72") (name "Net-(LED2-K)") (class "Default")
      (node (ref "LED2") (pin "1") (pinfunction "K_1") (pintype "passive"))
      (node (ref "R3") (pin "2") (pinfunction "2_2") (pintype "passive"))
    )
    (net (code "73") (name "Net-(LED3-K)") (class "Default")
      (node (ref "LED3") (pin "1") (pinfunction "K_1") (pintype "passive"))
      (node (ref "R4") (pin "2") (pinfunction "2_2") (pintype "passive"))
    )
    (net (code "74") (name "unconnected-(B1-LED8-Pad15)") (class "Default")
      (node (ref "B1") (pin "15") (pinfunction "LED8_15") (pintype "passive+no_connect"))
    )
    (net (code "75") (name "unconnected-(B1-LED9-Pad16)") (class "Default")
      (node (ref "B1") (pin "16") (pinfunction "LED9_16") (pintype "passive+no_connect"))
    )
    (net (code "76") (name "unconnected-(B1-LED10-Pad17)") (class "Default")
      (node (ref "B1") (pin "17") (pinfunction "LED10_17") (pintype "passive+no_connect"))
    )
    (net (code "77") (name "unconnected-(B1-LED11-Pad18)") (class "Default")
      (node (ref "B1") (pin "18") (pinfunction "LED11_18") (pintype "passive+no_connect"))
    )
    (net (code "78") (name "unconnected-(B1-LED12-Pad19)") (class "Default")
      (node (ref "B1") (pin "19") (pinfunction "LED12_19") (pintype "passive+no_connect"))
    )
    (net (code "79") (name "unconnected-(B1-LED13-Pad20)") (class "Default")
      (node (ref "B1") (pin "20") (pinfunction "LED13_20") (pintype "passive+no_connect"))
    )
    (net (code "80") (name "unconnected-(B1-LED14-Pad21)") (class "Default")
      (node (ref "B1") (pin "21") (pinfunction "LED14_21") (pintype "passive+no_connect"))
    )
    (net (code "81") (name "unconnected-(B1-LED15-Pad22)") (class "Default")
      (node (ref "B1") (pin "22") (pinfunction "LED15_22") (pintype "passive+no_connect"))
    )
    (net (code "82") (name "unconnected-(IC1-GND_2-Pad8)") (class "Default")
      (node (ref "IC1") (pin "8") (pinfunction "GND_2_8") (pintype "passive+no_connect"))
    )
    (net (code "83") (name "unconnected-(IC1-N.C._1-Pad6)") (class "Default")
      (node (ref "IC1") (pin "6") (pinfunction "N.C._1_6") (pintype "passive+no_connect"))
    )
    (net (code "84") (name "unconnected-(IC1-N.C._2-Pad7)") (class "Default")
      (node (ref "IC1") (pin "7") (pinfunction "N.C._2_7") (pintype "passive+no_connect"))
    )
    (net (code "85") (name "unconnected-(IC1-N.C._3-Pad9)") (class "Default")
      (node (ref "IC1") (pin "9") (pinfunction "N.C._3_9") (pintype "passive+no_connect"))
    )
    (net (code "86") (name "unconnected-(IC1-N.C._4-Pad10)") (class "Default")
      (node (ref "IC1") (pin "10") (pinfunction "N.C._4_10") (pintype "passive+no_connect"))
    )
    (net (code "87") (name "unconnected-(IC2-2A-Pad3)") (class "Default")
      (node (ref "IC2") (pin "3") (pinfunction "2A_3") (pintype "passive+no_connect"))
    )
    (net (code "88") (name "unconnected-(IC2-2Y-Pad4)") (class "Default")
      (node (ref "IC2") (pin "4") (pinfunction "2Y_4") (pintype "passive+no_connect"))
    )
    (net (code "89") (name "unconnected-(J2-Pad2)") (class "Default")
      (node (ref "J2") (pin "2") (pinfunction "2_2") (pintype "passive+no_connect"))
    )
    (net (code "90") (name "unconnected-(J2-Pad4)") (class "Default")
      (node (ref "J2") (pin "4") (pinfunction "4_4") (pintype "passive+no_connect"))
    )
    (net (code "91") (name "unconnected-(J2-Pad5)") (class "Default")
      (node (ref "J2") (pin "5") (pinfunction "5_5") (pintype "passive+no_connect"))
    )
    (net (code "92") (name "unconnected-(J2-Pad6)") (class "Default")
      (node (ref "J2") (pin "6") (pinfunction "6_6") (pintype "passive+no_connect"))
    )
    (net (code "93") (name "unconnected-(J2-Pad7)") (class "Default")
      (node (ref "J2") (pin "7") (pinfunction "7_7") (pintype "passive+no_connect"))
    )
    (net (code "94") (name "unconnected-(J2-Pad8)") (class "Default")
      (node (ref "J2") (pin "8") (pinfunction "8_8") (pintype "passive+no_connect"))
    )
    (net (code "95") (name "unconnected-(J2-Pad9)") (class "Default")
      (node (ref "J2") (pin "9") (pinfunction "9_9") (pintype "passive+no_connect"))
    )
    (net (code "96") (name "unconnected-(J2-Pad10)") (class "Default")
      (node (ref "J2") (pin "10") (pinfunction "10_10") (pintype "passive+no_connect"))
    )
    (net (code "97") (name "unconnected-(J2-Pad11)") (class "Default")
      (node (ref "J2") (pin "11") (pinfunction "11_11") (pintype "passive+no_connect"))
    )
    (net (code "98") (name "unconnected-(J2-Pad12)") (class "Default")
      (node (ref "J2") (pin "12") (pinfunction "12_12") (pintype "passive+no_connect"))
    )
    (net (code "99") (name "unconnected-(J2-Pad13)") (class "Default")
      (node (ref "J2") (pin "13") (pinfunction "13_13") (pintype "passive+no_connect"))
    )
    (net (code "100") (name "unconnected-(J2-Pad14)") (class "Default")
      (node (ref "J2") (pin "14") (pinfunction "14_14") (pintype "passive+no_connect"))
    )
    (net (code "101") (name "unconnected-(J2-Pad16)") (class "Default")
      (node (ref "J2") (pin "16") (pinfunction "16_16") (pintype "passive+no_connect"))
    )
    (net (code "102") (name "unconnected-(J2-Pad18)") (class "Default")
      (node (ref "J2") (pin "18") (pinfunction "18_18") (pintype "passive+no_connect"))
    )
    (net (code "103") (name "unconnected-(J2-Pad19)") (class "Default")
      (node (ref "J2") (pin "19") (pinfunction "19_19") (pintype "passive+no_connect"))
    )
    (net (code "104") (name "unconnected-(J2-Pad20)") (class "Default")
      (node (ref "J2") (pin "20") (pinfunction "20_20") (pintype "passive+no_connect"))
    )
    (net (code "105") (name "unconnected-(J2-Pad21)") (class "Default")
      (node (ref "J2") (pin "21") (pinfunction "21_21") (pintype "passive+no_connect"))
    )
    (net (code "106") (name "unconnected-(J2-Pad22)") (class "Default")
      (node (ref "J2") (pin "22") (pinfunction "22_22") (pintype "passive+no_connect"))
    )
    (net (code "107") (name "unconnected-(J2-Pad23)") (class "Default")
      (node (ref "J2") (pin "23") (pinfunction "23_23") (pintype "passive+no_connect"))
    )
    (net (code "108") (name "unconnected-(J2-Pad24)") (class "Default")
      (node (ref "J2") (pin "24") (pinfunction "24_24") (pintype "passive+no_connect"))
    )
    (net (code "109") (name "unconnected-(J2-Pad25)") (class "Default")
      (node (ref "J2") (pin "25") (pinfunction "25_25") (pintype "passive+no_connect"))
    )
    (net (code "110") (name "unconnected-(J2-Pad26)") (class "Default")
      (node (ref "J2") (pin "26") (pinfunction "26_26") (pintype "passive+no_connect"))
    )
    (net (code "111") (name "unconnected-(J2-Pad27)") (class "Default")
      (node (ref "J2") (pin "27") (pinfunction "27_27") (pintype "passive+no_connect"))
    )
    (net (code "112") (name "unconnected-(J2-Pad28)") (class "Default")
      (node (ref "J2") (pin "28") (pinfunction "28_28") (pintype "passive+no_connect"))
    )
    (net (code "113") (name "unconnected-(J2-Pad29)") (class "Default")
      (node (ref "J2") (pin "29") (pinfunction "29_29") (pintype "passive+no_connect"))
    )
    (net (code "114") (name "unconnected-(J2-Pad30)") (class "Default")
      (node (ref "J2") (pin "30") (pinfunction "30_30") (pintype "passive+no_connect"))
    )
    (net (code "115") (name "unconnected-(J2-Pad31)") (class "Default")
      (node (ref "J2") (pin "31") (pinfunction "31_31") (pintype "passive+no_connect"))
    )
    (net (code "116") (name "unconnected-(J2-Pad32)") (class "Default")
      (node (ref "J2") (pin "32") (pinfunction "32_32") (pintype "passive+no_connect"))
    )
    (net (code "117") (name "unconnected-(J2-Pad34)") (class "Default")
      (node (ref "J2") (pin "34") (pinfunction "34_34") (pintype "passive+no_connect"))
    )
    (net (code "118") (name "unconnected-(J2-Pad38)") (class "Default")
      (node (ref "J2") (pin "38") (pinfunction "38_38") (pintype "passive+no_connect"))
    )
    (net (code "119") (name "unconnected-(J2-Pad40)") (class "Default")
      (node (ref "J2") (pin "40") (pinfunction "40_40") (pintype "passive+no_connect"))
    )
    (net (code "120") (name "unconnected-(J4-ID-Pad4)") (class "Default")
      (node (ref "J4") (pin "4") (pinfunction "ID_4") (pintype "passive+no_connect"))
    )
    (net (code "121") (name "unconnected-(J4-pillar-Pad6)") (class "Default")
      (node (ref "J4") (pin "6") (pinfunction "pillar_6") (pintype "passive+no_connect"))
    )
    (net (code "122") (name "unconnected-(J4-pillar-Pad7)") (class "Default")
      (node (ref "J4") (pin "7") (pinfunction "pillar_7") (pintype "passive+no_connect"))
    )
    (net (code "123") (name "unconnected-(J4-wing-Pad8)") (class "Default")
      (node (ref "J4") (pin "8") (pinfunction "wing_8") (pintype "passive+no_connect"))
    )
    (net (code "124") (name "unconnected-(J4-wing-Pad9)") (class "Default")
      (node (ref "J4") (pin "9") (pinfunction "wing_9") (pintype "passive+no_connect"))
    )
  )
)
